# 220VAC-28VDC_Converter.net
KiCad netlist of a schematic drawn in EAGLE
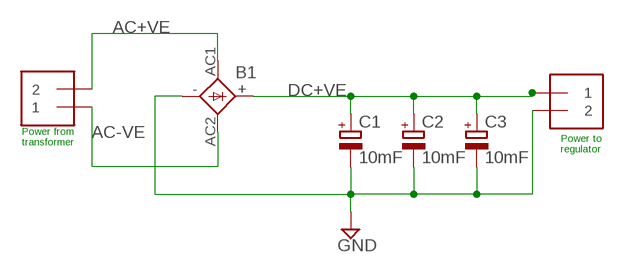
[diagram p0: schematic, sheet 1]

(export (version "E")
  (design (tool "Eeschema 10.0.6"))
  (components
    (comp (ref "B1")
      (value "KBU")
      (footprint "eagle-import:KBU")
      (libsource (lib "eagle-import") (part "KBU"))
    )
    (comp (ref "C1")
      (value "10mF")
      (footprint "eagle-import:EB35D")
      (libsource (lib "eagle-import") (part "CPOL-EUE10-35"))
    )
    (comp (ref "C2")
      (value "10mF")
      (footprint "eagle-import:EB35D")
      (libsource (lib "eagle-import") (part "CPOL-EUE10-35"))
    )
    (comp (ref "C3")
      (value "10mF")
      (footprint "eagle-import:EB35D")
      (libsource (lib "eagle-import") (part "CPOL-EUE10-35"))
    )
    (comp (ref "J1")
      (value "1X2-3.5MM")
      (footprint "eagle-import:1X2-3.5MM")
      (libsource (lib "eagle-import") (part "1X2-3.5MM"))
    )
    (comp (ref "J2")
      (value "1X2-3.5MM")
      (footprint "eagle-import:1X2-3.5MM")
      (libsource (lib "eagle-import") (part "1X2-3.5MM"))
    )
  )
  (nets
    (net (code "1") (name "/AC+VE") (class "Default")
      (node (ref "B1") (pin "AC1") (pinfunction "AC1_AC1") (pintype "passive"))
      (node (ref "J1") (pin "2") (pinfunction "2_2") (pintype "passive"))
    )
    (net (code "2") (name "/AC-VE") (class "Default")
      (node (ref "B1") (pin "AC2") (pinfunction "AC2_AC2") (pintype "passive"))
      (node (ref "J1") (pin "1") (pinfunction "1_1") (pintype "passive"))
    )
    (net (code "3") (name "/DC+VE") (class "Default")
      (node (ref "B1") (pin "+") (pinfunction "+_+") (pintype "passive"))
      (node (ref "C1") (pin "+") (pinfunction "+_+") (pintype "passive"))
      (node (ref "C2") (pin "+") (pinfunction "+_+") (pintype "passive"))
      (node (ref "C3") (pin "+") (pinfunction "+_+") (pintype "passive"))
      (node (ref "J2") (pin "1") (pinfunction "1_1") (pintype "passive"))
    )
    (net (code "4") (name "GND") (class "Default")
      (node (ref "B1") (pin "-") (pinfunction "-_-") (pintype "passive"))
      (node (ref "C1") (pin "-") (pinfunction "-_-") (pintype "passive"))
      (node (ref "C2") (pin "-") (pinfunction "-_-") (pintype "passive"))
      (node (ref "C3") (pin "-") (pinfunction "-_-") (pintype "passive"))
      (node (ref "J2") (pin "2") (pinfunction "2_2") (pintype "passive"))
    )
  )
)
